# sensor_board.net
KiCad netlist of a schematic drawn in EAGLE
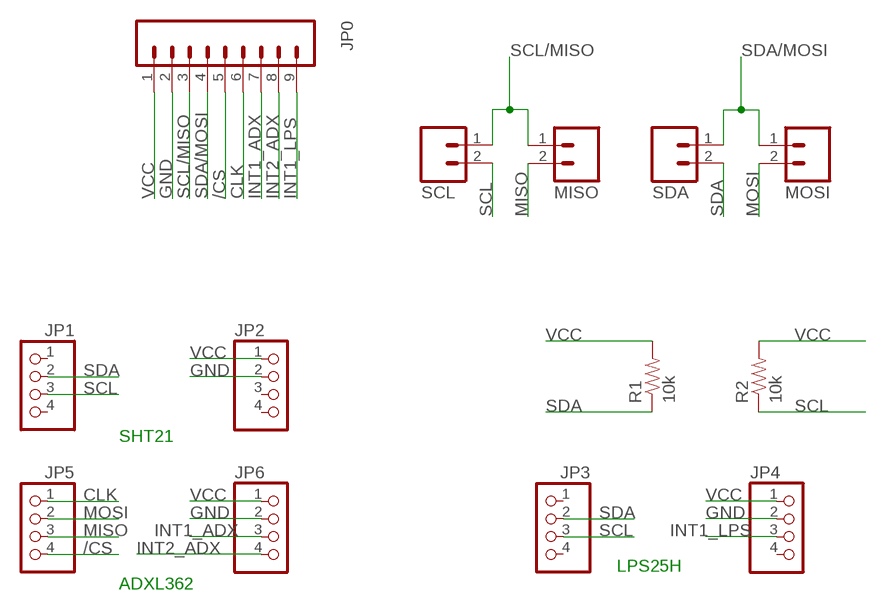
[diagram p0: schematic, sheet 1]

(export (version "E")
  (design (tool "Eeschema 10.0.6"))
  (components
    (comp (ref "JP0")
      (value "M09")
      (footprint "eagle-import:1X09")
      (libsource (lib "eagle-import") (part "M09"))
    )
    (comp (ref "JP1")
      (value "PINHD-1X4")
      (footprint "eagle-import:1X04")
      (libsource (lib "eagle-import") (part "PINHD-1X4"))
    )
    (comp (ref "JP2")
      (value "PINHD-1X4")
      (footprint "eagle-import:1X04")
      (libsource (lib "eagle-import") (part "PINHD-1X4"))
    )
    (comp (ref "JP3")
      (value "PINHD-1X4")
      (footprint "eagle-import:1X04")
      (libsource (lib "eagle-import") (part "PINHD-1X4"))
    )
    (comp (ref "JP4")
      (value "PINHD-1X4")
      (footprint "eagle-import:1X04")
      (libsource (lib "eagle-import") (part "PINHD-1X4"))
    )
    (comp (ref "JP5")
      (value "PINHD-1X4")
      (footprint "eagle-import:1X04")
      (libsource (lib "eagle-import") (part "PINHD-1X4"))
    )
    (comp (ref "JP6")
      (value "PINHD-1X4")
      (footprint "eagle-import:1X04")
      (libsource (lib "eagle-import") (part "PINHD-1X4"))
    )
    (comp (ref "MISO")
      (value "M02PTH")
      (footprint "eagle-import:1X02")
      (libsource (lib "eagle-import") (part "M02PTH"))
    )
    (comp (ref "MOSI")
      (value "M02PTH")
      (footprint "eagle-import:1X02")
      (libsource (lib "eagle-import") (part "M02PTH"))
    )
    (comp (ref "R1")
      (value "10k")
      (footprint "eagle-import:AXIAL-0.3")
      (libsource (lib "eagle-import") (part "10KOHM-1/4W5%(PTH)"))
    )
    (comp (ref "R2")
      (value "10k")
      (footprint "eagle-import:AXIAL-0.3")
      (libsource (lib "eagle-import") (part "10KOHM-1/4W5%(PTH)"))
    )
    (comp (ref "SCL")
      (value "M02PTH")
      (footprint "eagle-import:1X02")
      (libsource (lib "eagle-import") (part "M02PTH"))
    )
    (comp (ref "SDA")
      (value "M02PTH")
      (footprint "eagle-import:1X02")
      (libsource (lib "eagle-import") (part "M02PTH"))
    )
  )
  (nets
    (net (code "1") (name "/CLK") (class "Default")
      (node (ref "JP0") (pin "6") (pinfunction "6_6") (pintype "passive"))
      (node (ref "JP5") (pin "1") (pinfunction "1_1") (pintype "passive"))
    )
    (net (code "2") (name "/GND") (class "Default")
      (node (ref "JP0") (pin "2") (pinfunction "2_2") (pintype "passive"))
      (node (ref "JP2") (pin "2") (pinfunction "2_2") (pintype "passive"))
      (node (ref "JP4") (pin "2") (pinfunction "2_2") (pintype "passive"))
      (node (ref "JP6") (pin "2") (pinfunction "2_2") (pintype "passive"))
    )
    (net (code "3") (name "/INT1_ADX") (class "Default")
      (node (ref "JP0") (pin "7") (pinfunction "7_7") (pintype "passive"))
      (node (ref "JP6") (pin "3") (pinfunction "3_3") (pintype "passive"))
    )
    (net (code "4") (name "/INT1_LPS") (class "Default")
      (node (ref "JP0") (pin "9") (pinfunction "9_9") (pintype "passive"))
      (node (ref "JP4") (pin "3") (pinfunction "3_3") (pintype "passive"))
    )
    (net (code "5") (name "/INT2_ADX") (class "Default")
      (node (ref "JP0") (pin "8") (pinfunction "8_8") (pintype "passive"))
      (node (ref "JP6") (pin "4") (pinfunction "4_4") (pintype "passive"))
    )
    (net (code "6") (name "/MISO") (class "Default")
      (node (ref "JP5") (pin "3") (pinfunction "3_3") (pintype "passive"))
      (node (ref "MISO") (pin "2") (pinfunction "2_2") (pintype "passive"))
    )
    (net (code "7") (name "/MOSI") (class "Default")
      (node (ref "JP5") (pin "2") (pinfunction "2_2") (pintype "passive"))
      (node (ref "MOSI") (pin "2") (pinfunction "2_2") (pintype "passive"))
    )
    (net (code "8") (name "/SCL") (class "Default")
      (node (ref "JP1") (pin "3") (pinfunction "3_3") (pintype "passive"))
      (node (ref "JP3") (pin "3") (pinfunction "3_3") (pintype "passive"))
      (node (ref "R2") (pin "P$1") (pinfunction "1_P$1") (pintype "passive"))
      (node (ref "SCL") (pin "2") (pinfunction "2_2") (pintype "passive"))
    )
    (net (code "9") (name "/SCL{slash}MISO") (class "Default")
      (node (ref "JP0") (pin "3") (pinfunction "3_3") (pintype "passive"))
      (node (ref "MISO") (pin "1") (pinfunction "1_1") (pintype "passive"))
      (node (ref "SCL") (pin "1") (pinfunction "1_1") (pintype "passive"))
    )
    (net (code "10") (name "/SDA") (class "Default")
      (node (ref "JP1") (pin "2") (pinfunction "2_2") (pintype "passive"))
      (node (ref "JP3") (pin "2") (pinfunction "2_2") (pintype "passive"))
      (node (ref "R1") (pin "P$1") (pinfunction "1_P$1") (pintype "passive"))
      (node (ref "SDA") (pin "2") (pinfunction "2_2") (pintype "passive"))
    )
    (net (code "11") (name "/SDA{slash}MOSI") (class "Default")
      (node (ref "JP0") (pin "4") (pinfunction "4_4") (pintype "passive"))
      (node (ref "MOSI") (pin "1") (pinfunction "1_1") (pintype "passive"))
      (node (ref "SDA") (pin "1") (pinfunction "1_1") (pintype "passive"))
    )
    (net (code "12") (name "/VCC") (class "Default")
      (node (ref "JP0") (pin "1") (pinfunction "1_1") (pintype "passive"))
      (node (ref "JP2") (pin "1") (pinfunction "1_1") (pintype "passive"))
      (node (ref "JP4") (pin "1") (pinfunction "1_1") (pintype "passive"))
      (node (ref "JP6") (pin "1") (pinfunction "1_1") (pintype "passive"))
      (node (ref "R1") (pin "P$2") (pinfunction "2_P$2") (pintype "passive"))
      (node (ref "R2") (pin "P$2") (pinfunction "2_P$2") (pintype "passive"))
    )
    (net (code "13") (name "/{slash}CS") (class "Default")
      (node (ref "JP0") (pin "5") (pinfunction "5_5") (pintype "passive"))
      (node (ref "JP5") (pin "4") (pinfunction "4_4") (pintype "passive"))
    )
    (net (code "14") (name "unconnected-(JP1-Pad1)") (class "Default")
      (node (ref "JP1") (pin "1") (pinfunction "1_1") (pintype "passive"))
    )
    (net (code "15") (name "unconnected-(JP1-Pad4)") (class "Default")
      (node (ref "JP1") (pin "4") (pinfunction "4_4") (pintype "passive"))
    )
    (net (code "16") (name "unconnected-(JP2-Pad3)") (class "Default")
      (node (ref "JP2") (pin "3") (pinfunction "3_3") (pintype "passive"))
    )
    (net (code "17") (name "unconnected-(JP2-Pad4)") (class "Default")
      (node (ref "JP2") (pin "4") (pinfunction "4_4") (pintype "passive"))
    )
    (net (code "18") (name "unconnected-(JP3-Pad1)") (class "Default")
      (node (ref "JP3") (pin "1") (pinfunction "1_1") (pintype "passive"))
    )
    (net (code "19") (name "unconnected-(JP3-Pad4)") (class "Default")
      (node (ref "JP3") (pin "4") (pinfunction "4_4") (pintype "passive"))
    )
    (net (code "20") (name "unconnected-(JP4-Pad4)") (class "Default")
      (node (ref "JP4") (pin "4") (pinfunction "4_4") (pintype "passive"))
    )
  )
)
